# GPS_Tracker.net
KiCad netlist of a schematic drawn in EAGLE
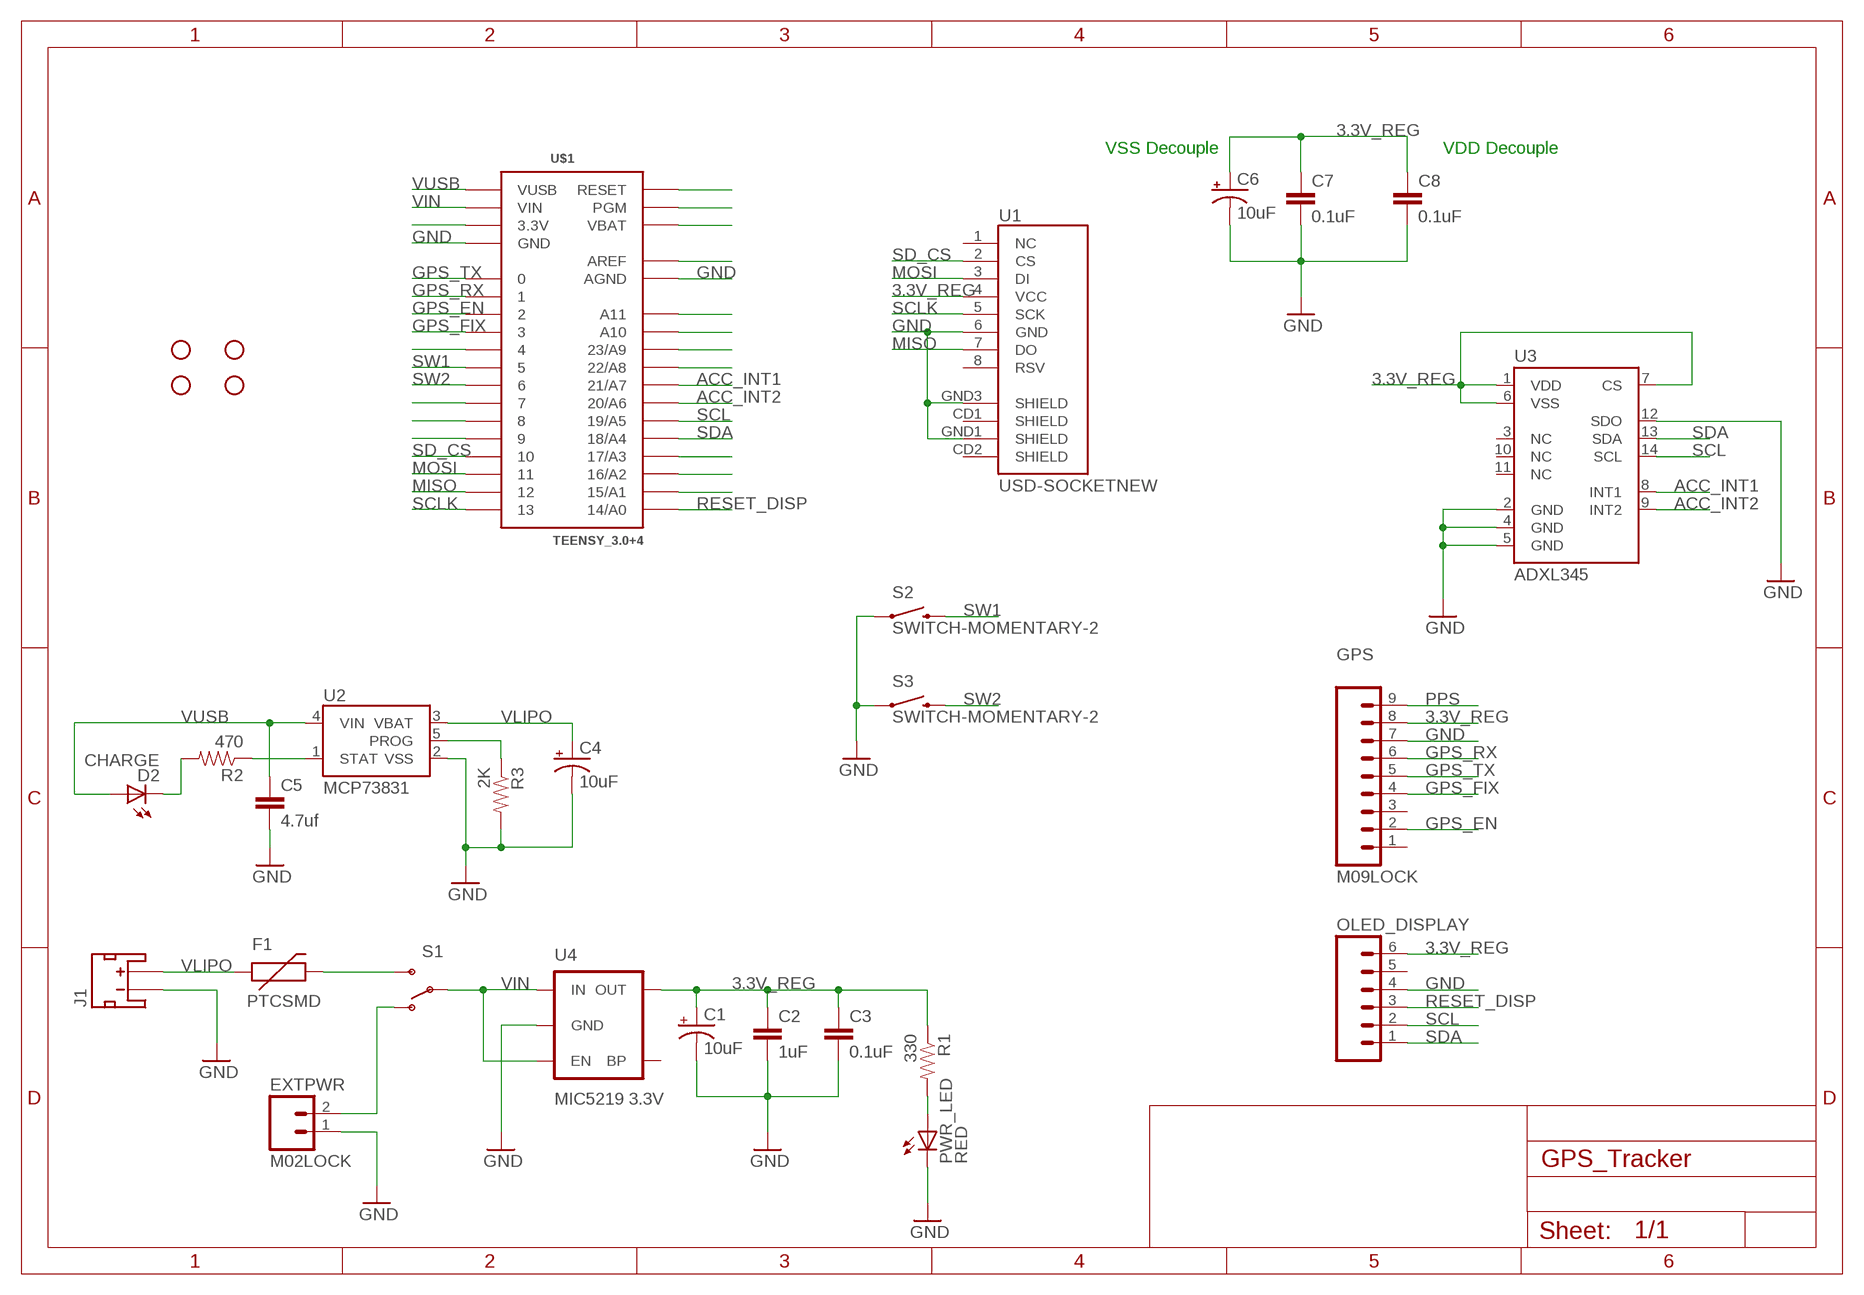
[diagram p0: schematic, sheet 1]

(export (version "E")
  (design (tool "Eeschema 10.0.6"))
  (components
    (comp (ref "C1")
      (value "10uF")
      (footprint "eagle-import:EIA3216")
      (libsource (lib "eagle-import") (part "CAP_POL1206"))
    )
    (comp (ref "C2")
      (value "1uF")
      (footprint "eagle-import:0402-CAP")
      (libsource (lib "eagle-import") (part "CAP0402-CAP"))
    )
    (comp (ref "C3")
      (value "0.1uF")
      (footprint "eagle-import:0402-CAP")
      (libsource (lib "eagle-import") (part "CAP0402-CAP"))
    )
    (comp (ref "C4")
      (value "10uF")
      (footprint "eagle-import:EIA3216")
      (libsource (lib "eagle-import") (part "CAP_POL1206"))
    )
    (comp (ref "C5")
      (value "4.7uf")
      (footprint "eagle-import:0402-CAP")
      (libsource (lib "eagle-import") (part "CAP0402-CAP"))
    )
    (comp (ref "C6")
      (value "10uF")
      (footprint "eagle-import:EIA3216")
      (libsource (lib "eagle-import") (part "CAP_POL1206"))
    )
    (comp (ref "C7")
      (value "0.1uF")
      (footprint "eagle-import:0402-CAP")
      (libsource (lib "eagle-import") (part "CAP0402-CAP"))
    )
    (comp (ref "C8")
      (value "0.1uF")
      (footprint "eagle-import:0402-CAP")
      (libsource (lib "eagle-import") (part "CAP0402-CAP"))
    )
    (comp (ref "D2")
      (value "CHARGE")
      (footprint "eagle-import:LED-0603")
      (libsource (lib "eagle-import") (part "LED-YELLOW0603"))
    )
    (comp (ref "EXTPWR")
      (value "M02LOCK")
      (footprint "eagle-import:1X02_LOCK")
      (libsource (lib "eagle-import") (part "M02LOCK"))
    )
    (comp (ref "F1")
      (value "PTCSMD")
      (footprint "eagle-import:PTC-1206")
      (libsource (lib "eagle-import") (part "PTCSMD"))
    )
    (comp (ref "GPS")
      (value "M09LOCK")
      (footprint "eagle-import:1X09_LOCK")
      (libsource (lib "eagle-import") (part "M09LOCK"))
    )
    (comp (ref "J1")
      (value "JST_2MM_MALE")
      (footprint "eagle-import:JST-2-SMD")
      (libsource (lib "eagle-import") (part "JST_2MM_MALE"))
    )
    (comp (ref "OLED_DISPLAY")
      (value "M06LOCK")
      (footprint "eagle-import:1X06_LOCK")
      (libsource (lib "eagle-import") (part "M06LOCK"))
    )
    (comp (ref "PWR_LED")
      (value "RED")
      (footprint "eagle-import:LED-0603")
      (libsource (lib "eagle-import") (part "LED-RED0603"))
    )
    (comp (ref "R1")
      (value "330")
      (footprint "eagle-import:0402-RES")
      (libsource (lib "eagle-import") (part "RESISTOR0402-RES"))
    )
    (comp (ref "R2")
      (value "470")
      (footprint "eagle-import:0402-RES")
      (libsource (lib "eagle-import") (part "RESISTOR0402-RES"))
    )
    (comp (ref "R3")
      (value "2K")
      (footprint "eagle-import:0402-RES")
      (libsource (lib "eagle-import") (part "RESISTOR0402-RES"))
    )
    (comp (ref "S1")
      (value "SWITCH-SPDTSMD")
      (footprint "eagle-import:AYZ0202")
      (libsource (lib "eagle-import") (part "SWITCH-SPDTSMD"))
    )
    (comp (ref "S2")
      (value "SWITCH-MOMENTARY-2")
      (footprint "eagle-import:TACTILE_SWITCH_TALL")
      (libsource (lib "eagle-import") (part "SWITCH-MOMENTARY-2"))
    )
    (comp (ref "S3")
      (value "SWITCH-MOMENTARY-2")
      (footprint "eagle-import:TACTILE_SWITCH_TALL")
      (libsource (lib "eagle-import") (part "SWITCH-MOMENTARY-2"))
    )
    (comp (ref "STANDOFF1")
      (value "STAND-OFF")
      (footprint "eagle-import:STAND-OFF")
      (libsource (lib "eagle-import") (part "STAND-OFF"))
    )
    (comp (ref "STANDOFF2")
      (value "STAND-OFF")
      (footprint "eagle-import:STAND-OFF")
      (libsource (lib "eagle-import") (part "STAND-OFF"))
    )
    (comp (ref "STANDOFF3")
      (value "STAND-OFF")
      (footprint "eagle-import:STAND-OFF")
      (libsource (lib "eagle-import") (part "STAND-OFF"))
    )
    (comp (ref "STANDOFF4")
      (value "STAND-OFF")
      (footprint "eagle-import:STAND-OFF")
      (libsource (lib "eagle-import") (part "STAND-OFF"))
    )
    (comp (ref "U$1")
      (value "TEENSY_3.0+4")
      (footprint "eagle-import:TEENSY_3.0+4")
      (libsource (lib "eagle-import") (part "TEENSY_3.0+4"))
    )
    (comp (ref "U1")
      (value "USD-SOCKETNEW")
      (footprint "eagle-import:MICRO-SD-SOCKET-PP")
      (libsource (lib "eagle-import") (part "USD-SOCKETNEW"))
    )
    (comp (ref "U2")
      (value "MCP73831")
      (footprint "eagle-import:SOT23-5")
      (libsource (lib "eagle-import") (part "MCP73831"))
    )
    (comp (ref "U3")
      (value "ADXL345")
      (footprint "eagle-import:LGA14")
      (libsource (lib "eagle-import") (part "ADXL345"))
    )
    (comp (ref "U4")
      (value "MIC5219 3.3V")
      (footprint "eagle-import:SOT23-5")
      (libsource (lib "eagle-import") (part "V_REG_MIC52193.3V"))
    )
  )
  (nets
    (net (code "1") (name "/3.3V_REG") (class "Default")
      (node (ref "C1") (pin "A") (pinfunction "+_A") (pintype "passive"))
      (node (ref "C2") (pin "1") (pinfunction "1_1") (pintype "passive"))
      (node (ref "C3") (pin "1") (pinfunction "1_1") (pintype "passive"))
      (node (ref "C6") (pin "A") (pinfunction "+_A") (pintype "passive"))
      (node (ref "C7") (pin "1") (pinfunction "1_1") (pintype "passive"))
      (node (ref "C8") (pin "1") (pinfunction "1_1") (pintype "passive"))
      (node (ref "GPS") (pin "8") (pinfunction "8_8") (pintype "passive"))
      (node (ref "OLED_DISPLAY") (pin "6") (pinfunction "6_6") (pintype "passive"))
      (node (ref "R1") (pin "1") (pinfunction "1_1") (pintype "passive"))
      (node (ref "U1") (pin "4") (pinfunction "VCC_4") (pintype "bidirectional"))
      (node (ref "U3") (pin "1") (pinfunction "VDD_1") (pintype "bidirectional"))
      (node (ref "U3") (pin "6") (pinfunction "VSS_6") (pintype "bidirectional"))
      (node (ref "U3") (pin "7") (pinfunction "CS_7") (pintype "bidirectional"))
      (node (ref "U4") (pin "5") (pinfunction "OUT_5") (pintype "passive"))
    )
    (net (code "2") (name "/ACC_INT1") (class "Default")
      (node (ref "U$1") (pin "21/A7") (pinfunction "21/A7_21/A7") (pintype "bidirectional"))
      (node (ref "U3") (pin "8") (pinfunction "INT1_8") (pintype "bidirectional"))
    )
    (net (code "3") (name "/ACC_INT2") (class "Default")
      (node (ref "U$1") (pin "20/A6") (pinfunction "20/A6_20/A6") (pintype "bidirectional"))
      (node (ref "U3") (pin "9") (pinfunction "INT2_9") (pintype "bidirectional"))
    )
    (net (code "4") (name "/GPS_EN") (class "Default")
      (node (ref "GPS") (pin "2") (pinfunction "2_2") (pintype "passive"))
      (node (ref "U$1") (pin "2") (pinfunction "2_2") (pintype "bidirectional"))
    )
    (net (code "5") (name "/GPS_FIX") (class "Default")
      (node (ref "GPS") (pin "4") (pinfunction "4_4") (pintype "passive"))
      (node (ref "U$1") (pin "3") (pinfunction "3_3") (pintype "bidirectional"))
    )
    (net (code "6") (name "/GPS_RX") (class "Default")
      (node (ref "GPS") (pin "6") (pinfunction "6_6") (pintype "passive"))
      (node (ref "U$1") (pin "1") (pinfunction "1_1") (pintype "bidirectional"))
    )
    (net (code "7") (name "/GPS_TX") (class "Default")
      (node (ref "GPS") (pin "5") (pinfunction "5_5") (pintype "passive"))
      (node (ref "U$1") (pin "0") (pinfunction "0_0") (pintype "bidirectional"))
    )
    (net (code "8") (name "/MISO") (class "Default")
      (node (ref "U$1") (pin "12") (pinfunction "12_12") (pintype "bidirectional"))
      (node (ref "U1") (pin "7") (pinfunction "DO_7") (pintype "bidirectional"))
    )
    (net (code "9") (name "/MOSI") (class "Default")
      (node (ref "U$1") (pin "11") (pinfunction "11_11") (pintype "bidirectional"))
      (node (ref "U1") (pin "3") (pinfunction "DI_3") (pintype "bidirectional"))
    )
    (net (code "10") (name "/PPS") (class "Default")
      (node (ref "GPS") (pin "9") (pinfunction "9_9") (pintype "passive"))
    )
    (net (code "11") (name "/RESET_DISP") (class "Default")
      (node (ref "OLED_DISPLAY") (pin "3") (pinfunction "3_3") (pintype "passive"))
      (node (ref "U$1") (pin "14/A0") (pinfunction "14/A0_14/A0") (pintype "bidirectional"))
    )
    (net (code "12") (name "/SCL") (class "Default")
      (node (ref "OLED_DISPLAY") (pin "2") (pinfunction "2_2") (pintype "passive"))
      (node (ref "U$1") (pin "19/A5") (pinfunction "19/A5_19/A5") (pintype "bidirectional"))
      (node (ref "U3") (pin "14") (pinfunction "SCL_14") (pintype "bidirectional"))
    )
    (net (code "13") (name "/SCLK") (class "Default")
      (node (ref "U$1") (pin "13") (pinfunction "13_13") (pintype "bidirectional"))
      (node (ref "U1") (pin "5") (pinfunction "SCK_5") (pintype "bidirectional"))
    )
    (net (code "14") (name "/SDA") (class "Default")
      (node (ref "OLED_DISPLAY") (pin "1") (pinfunction "1_1") (pintype "passive"))
      (node (ref "U$1") (pin "18/A4") (pinfunction "18/A4_18/A4") (pintype "bidirectional"))
      (node (ref "U3") (pin "13") (pinfunction "SDA_13") (pintype "bidirectional"))
    )
    (net (code "15") (name "/SD_CS") (class "Default")
      (node (ref "U$1") (pin "10") (pinfunction "10_10") (pintype "bidirectional"))
      (node (ref "U1") (pin "2") (pinfunction "CS_2") (pintype "bidirectional"))
    )
    (net (code "16") (name "/SW1") (class "Default")
      (node (ref "S2") (pin "B2") (pinfunction "2_B2") (pintype "passive"))
      (node (ref "U$1") (pin "5") (pinfunction "5_5") (pintype "bidirectional"))
    )
    (net (code "17") (name "/SW2") (class "Default")
      (node (ref "S3") (pin "B2") (pinfunction "2_B2") (pintype "passive"))
      (node (ref "U$1") (pin "6") (pinfunction "6_6") (pintype "bidirectional"))
    )
    (net (code "18") (name "/VIN") (class "Default")
      (node (ref "S1") (pin "2") (pinfunction "P_2") (pintype "passive"))
      (node (ref "U$1") (pin "VIN") (pinfunction "VIN_VIN") (pintype "power_in"))
      (node (ref "U4") (pin "1") (pinfunction "IN_1") (pintype "input"))
      (node (ref "U4") (pin "3") (pinfunction "EN_3") (pintype "input"))
    )
    (net (code "19") (name "/VLIPO") (class "Default")
      (node (ref "C4") (pin "A") (pinfunction "+_A") (pintype "passive"))
      (node (ref "F1") (pin "1") (pinfunction "1_1") (pintype "bidirectional"))
      (node (ref "J1") (pin "2") (pinfunction "+_2") (pintype "bidirectional"))
      (node (ref "U2") (pin "3") (pinfunction "VBAT_3") (pintype "power_in"))
    )
    (net (code "20") (name "/VUSB") (class "Default")
      (node (ref "C5") (pin "1") (pinfunction "1_1") (pintype "passive"))
      (node (ref "D2") (pin "A") (pinfunction "A_A") (pintype "passive"))
      (node (ref "U$1") (pin "VUSB") (pinfunction "VUSB_VUSB") (pintype "power_in"))
      (node (ref "U2") (pin "4") (pinfunction "VIN_4") (pintype "power_in"))
    )
    (net (code "21") (name "GND") (class "Default")
      (node (ref "C1") (pin "C") (pinfunction "-_C") (pintype "passive"))
      (node (ref "C2") (pin "2") (pinfunction "2_2") (pintype "passive"))
      (node (ref "C3") (pin "2") (pinfunction "2_2") (pintype "passive"))
      (node (ref "C4") (pin "C") (pinfunction "-_C") (pintype "passive"))
      (node (ref "C5") (pin "2") (pinfunction "2_2") (pintype "passive"))
      (node (ref "C6") (pin "C") (pinfunction "-_C") (pintype "passive"))
      (node (ref "C7") (pin "2") (pinfunction "2_2") (pintype "passive"))
      (node (ref "C8") (pin "2") (pinfunction "2_2") (pintype "passive"))
      (node (ref "EXTPWR") (pin "1") (pinfunction "1_1") (pintype "passive"))
      (node (ref "GPS") (pin "7") (pinfunction "7_7") (pintype "passive"))
      (node (ref "J1") (pin "1") (pinfunction "-_1") (pintype "bidirectional"))
      (node (ref "OLED_DISPLAY") (pin "4") (pinfunction "4_4") (pintype "passive"))
      (node (ref "PWR_LED") (pin "C") (pinfunction "C_C") (pintype "passive"))
      (node (ref "R3") (pin "2") (pinfunction "2_2") (pintype "passive"))
      (node (ref "S2") (pin "A2") (pinfunction "1_A2") (pintype "passive"))
      (node (ref "S3") (pin "A2") (pinfunction "1_A2") (pintype "passive"))
      (node (ref "U$1") (pin "AGND") (pinfunction "AGND_AGND") (pintype "power_in"))
      (node (ref "U$1") (pin "GND") (pinfunction "GND_GND") (pintype "power_in"))
      (node (ref "U$1") (pin "GND1") (pinfunction "GND_GND1") (pintype "power_in"))
      (node (ref "U1") (pin "6") (pinfunction "GND_6") (pintype "bidirectional"))
      (node (ref "U1") (pin "GND1") (pinfunction "SHIELD_GND1") (pintype "bidirectional"))
      (node (ref "U1") (pin "GND3") (pinfunction "SHIELD_GND3") (pintype "bidirectional"))
      (node (ref "U2") (pin "2") (pinfunction "VSS_2") (pintype "power_in"))
      (node (ref "U3") (pin "12") (pinfunction "SDO_12") (pintype "bidirectional"))
      (node (ref "U3") (pin "2") (pinfunction "GND_2") (pintype "bidirectional"))
      (node (ref "U3") (pin "4") (pinfunction "GND_4") (pintype "bidirectional"))
      (node (ref "U3") (pin "5") (pinfunction "GND_5") (pintype "bidirectional"))
      (node (ref "U4") (pin "2") (pinfunction "GND_2") (pintype "input"))
    )
    (net (code "22") (name "Net-(D2-PadC)") (class "Default")
      (node (ref "D2") (pin "C") (pinfunction "C_C") (pintype "passive"))
      (node (ref "R2") (pin "2") (pinfunction "2_2") (pintype "passive"))
    )
    (net (code "23") (name "Net-(PWR_LED-PadA)") (class "Default")
      (node (ref "PWR_LED") (pin "A") (pinfunction "A_A") (pintype "passive"))
      (node (ref "R1") (pin "2") (pinfunction "2_2") (pintype "passive"))
    )
    (net (code "24") (name "Net-(S1-O)") (class "Default")
      (node (ref "EXTPWR") (pin "2") (pinfunction "2_2") (pintype "passive"))
      (node (ref "S1") (pin "1") (pinfunction "O_1") (pintype "passive"))
    )
    (net (code "25") (name "Net-(S1-S)") (class "Default")
      (node (ref "F1") (pin "2") (pinfunction "2_2") (pintype "bidirectional"))
      (node (ref "S1") (pin "3") (pinfunction "S_3") (pintype "passive"))
    )
    (net (code "26") (name "Net-(U$1-3.3V-Pad3.3V1)") (class "Default")
      (node (ref "U$1") (pin "3.3V") (pinfunction "3.3V_3.3V") (pintype "power_in"))
      (node (ref "U$1") (pin "3.3V1") (pinfunction "3.3V_3.3V1") (pintype "power_in"))
    )
    (net (code "27") (name "Net-(U2-PROG)") (class "Default")
      (node (ref "R3") (pin "1") (pinfunction "1_1") (pintype "passive"))
      (node (ref "U2") (pin "5") (pinfunction "PROG_5") (pintype "input"))
    )
    (net (code "28") (name "Net-(U2-STAT)") (class "Default")
      (node (ref "R2") (pin "1") (pinfunction "1_1") (pintype "passive"))
      (node (ref "U2") (pin "1") (pinfunction "STAT_1") (pintype "output"))
    )
    (net (code "29") (name "unconnected-(GPS-Pad1)") (class "Default")
      (node (ref "GPS") (pin "1") (pinfunction "1_1") (pintype "passive"))
    )
    (net (code "30") (name "unconnected-(GPS-Pad3)") (class "Default")
      (node (ref "GPS") (pin "3") (pinfunction "3_3") (pintype "passive"))
    )
    (net (code "31") (name "unconnected-(J1-PAD1-PadNC1)") (class "Default")
      (node (ref "J1") (pin "NC1") (pinfunction "PAD1_NC1") (pintype "bidirectional"))
    )
    (net (code "32") (name "unconnected-(J1-PAD2-PadNC2)") (class "Default")
      (node (ref "J1") (pin "NC2") (pinfunction "PAD2_NC2") (pintype "bidirectional"))
    )
    (net (code "33") (name "unconnected-(OLED_DISPLAY-Pad5)") (class "Default")
      (node (ref "OLED_DISPLAY") (pin "5") (pinfunction "5_5") (pintype "passive"))
    )
    (net (code "34") (name "unconnected-(U$1-Pad4)") (class "Default")
      (node (ref "U$1") (pin "4") (pinfunction "4_4") (pintype "bidirectional"))
    )
    (net (code "35") (name "unconnected-(U$1-Pad7)") (class "Default")
      (node (ref "U$1") (pin "7") (pinfunction "7_7") (pintype "bidirectional"))
    )
    (net (code "36") (name "unconnected-(U$1-Pad8)") (class "Default")
      (node (ref "U$1") (pin "8") (pinfunction "8_8") (pintype "bidirectional"))
    )
    (net (code "37") (name "unconnected-(U$1-Pad9)") (class "Default")
      (node (ref "U$1") (pin "9") (pinfunction "9_9") (pintype "bidirectional"))
    )
    (net (code "38") (name "unconnected-(U$1-Pad15{slash}A1)") (class "Default")
      (node (ref "U$1") (pin "15/A1") (pinfunction "15/A1_15/A1") (pintype "bidirectional"))
    )
    (net (code "39") (name "unconnected-(U$1-Pad16{slash}A2)") (class "Default")
      (node (ref "U$1") (pin "16/A2") (pinfunction "16/A2_16/A2") (pintype "bidirectional"))
    )
    (net (code "40") (name "unconnected-(U$1-Pad17{slash}A3)") (class "Default")
      (node (ref "U$1") (pin "17/A3") (pinfunction "17/A3_17/A3") (pintype "bidirectional"))
    )
    (net (code "41") (name "unconnected-(U$1-Pad22{slash}A8)") (class "Default")
      (node (ref "U$1") (pin "22/A8") (pinfunction "22/A8_22/A8") (pintype "bidirectional"))
    )
    (net (code "42") (name "unconnected-(U$1-Pad23{slash}A9)") (class "Default")
      (node (ref "U$1") (pin "23/A9") (pinfunction "23/A9_23/A9") (pintype "bidirectional"))
    )
    (net (code "43") (name "unconnected-(U$1-PadA10)") (class "Default")
      (node (ref "U$1") (pin "A10") (pinfunction "A10_A10") (pintype "bidirectional"))
    )
    (net (code "44") (name "unconnected-(U$1-PadA11)") (class "Default")
      (node (ref "U$1") (pin "A11") (pinfunction "A11_A11") (pintype "bidirectional"))
    )
    (net (code "45") (name "unconnected-(U$1-PadAREF)") (class "Default")
      (node (ref "U$1") (pin "AREF") (pinfunction "AREF_AREF") (pintype "power_in"))
    )
    (net (code "46") (name "unconnected-(U$1-PadPGM)") (class "Default")
      (node (ref "U$1") (pin "PGM") (pinfunction "PGM_PGM") (pintype "bidirectional"))
    )
    (net (code "47") (name "unconnected-(U$1-PadRESET)") (class "Default")
      (node (ref "U$1") (pin "RESET") (pinfunction "RESET_RESET") (pintype "bidirectional"))
    )
    (net (code "48") (name "unconnected-(U$1-PadVBAT)") (class "Default")
      (node (ref "U$1") (pin "VBAT") (pinfunction "VBAT_VBAT") (pintype "power_in"))
    )
    (net (code "49") (name "unconnected-(U1-NC-Pad1)") (class "Default")
      (node (ref "U1") (pin "1") (pinfunction "NC_1") (pintype "bidirectional"))
    )
    (net (code "50") (name "unconnected-(U1-RSV-Pad8)") (class "Default")
      (node (ref "U1") (pin "8") (pinfunction "RSV_8") (pintype "bidirectional"))
    )
    (net (code "51") (name "unconnected-(U1-SHIELD-PadCD1)") (class "Default")
      (node (ref "U1") (pin "CD1") (pinfunction "SHIELD_CD1") (pintype "bidirectional"))
    )
    (net (code "52") (name "unconnected-(U1-SHIELD-PadCD2)") (class "Default")
      (node (ref "U1") (pin "CD2") (pinfunction "SHIELD_CD2") (pintype "bidirectional"))
    )
    (net (code "53") (name "unconnected-(U3-NC-Pad3)") (class "Default")
      (node (ref "U3") (pin "3") (pinfunction "NC_3") (pintype "bidirectional"))
    )
    (net (code "54") (name "unconnected-(U3-NC-Pad10)") (class "Default")
      (node (ref "U3") (pin "10") (pinfunction "NC_10") (pintype "bidirectional"))
    )
    (net (code "55") (name "unconnected-(U3-NC-Pad11)") (class "Default")
      (node (ref "U3") (pin "11") (pinfunction "NC_11") (pintype "bidirectional"))
    )
    (net (code "56") (name "unconnected-(U4-BP-Pad4)") (class "Default")
      (node (ref "U4") (pin "4") (pinfunction "BP_4") (pintype "input"))
    )
  )
)
